# ConnectorIn.net
KiCad netlist of a schematic drawn in Altium Designer
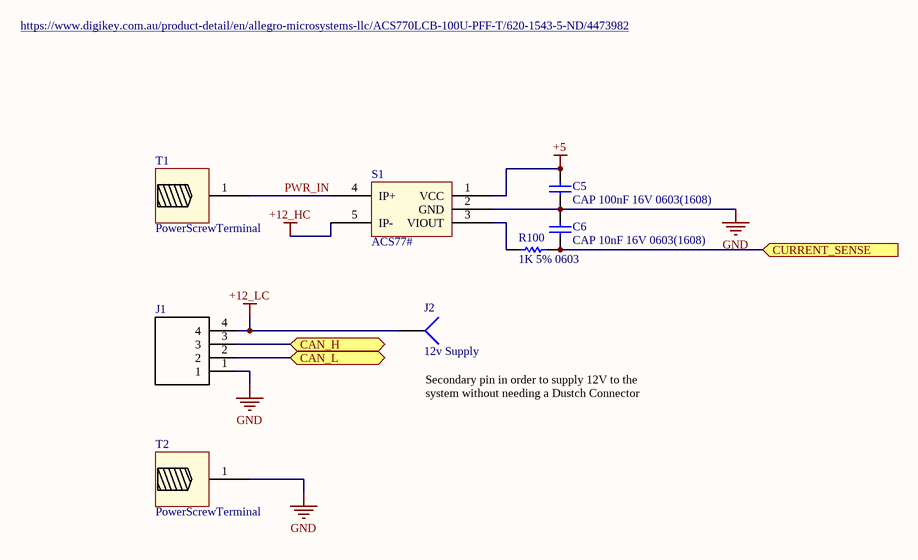
[diagram p0: ConnectorIn.SchDoc]

(export (version "E")
  (design (tool "Eeschema 10.0.6"))
  (components
    (comp (ref "C5")
      (value "CAP 100nF 16V 0603(1608)")
      (footprint "CAPC0603(1608)100_M")
      (description "CAP 100nF 16V ±5% 0603 (1608 Metric) Thickness 1mm SMD")
      (fields (field (name "TOLERANCE") "Â±5%"))
      (libsource (lib "Altium Content Vault") (part "CAP"))
    )
    (comp (ref "C6")
      (value "CAP 10nF 16V 0603(1608)")
      (footprint "CAPC0603(1608)100_M")
      (description "CAP 10nF 16V ±5% 0603 (1608 Metric) Thickness 1mm SMD")
      (fields (field (name "TOLERANCE") "Â±5%"))
      (libsource (lib "Altium Content Vault") (part "CAP"))
    )
    (comp (ref "J1")
      (value "DT15-4P")
      (footprint "TE_DT15-4P")
      (description "DT Series 4 Position 16 AWG Flange Mount Male Pin Through Hole Receptacle Header")
      (fields (field (name "MF") "TE Connectivity") (field (name "DIGI-KEY_PART_NUMBER") "1734-1030-ND"))
      (libsource (lib "DT15-4P") (part "DT15-4P"))
    )
    (comp (ref "J2")
      (value "12v Supply")
      (footprint "PIN1")
      (description "Socket")
      (fields (field (name "PUBLISHER") "Altium Limited"))
      (libsource (lib "Miscellaneous Connectors") (part "Socket"))
    )
    (comp (ref "R100")
      (value "1K 5% 0603")
      (footprint "RESC0603(1608)_L")
      (description "1K 0.1W 5% 0603 (1608 Metric)  SMD")
      (fields (field (name "TOLERANCE") "5 %") (field (name "POWER") "0.1 W"))
      (libsource (lib "Altium Content Vault") (part "RES"))
    )
    (comp (ref "S1")
      (value "ACS77#")
      (footprint "ACS77#")
      (libsource (lib "HC_PCBConnector") (part "ACS77#"))
    )
    (comp (ref "T1")
      (value "PowerScrewTerminal")
      (footprint "WE_REDCUBE_74650195R")
      (libsource (lib "HC_PCBConnector") (part "PowerScrewTerminal"))
    )
    (comp (ref "T2")
      (value "PowerScrewTerminal")
      (footprint "WE_REDCUBE_74650195R")
      (libsource (lib "HC_PCBConnector") (part "PowerScrewTerminal"))
    )
  )
  (nets
    (net (code "1") (name "+5") (class "Default")
      (node (ref "C5") (pin "2") (pinfunction "2_2") (pintype "passive"))
      (node (ref "S1") (pin "1") (pinfunction "VCC_1") (pintype "passive"))
    )
    (net (code "2") (name "+12_HC") (class "Default")
      (node (ref "S1") (pin "5") (pinfunction "IP-_5") (pintype "passive"))
    )
    (net (code "3") (name "+12_LC") (class "Default")
      (node (ref "J1") (pin "4") (pinfunction "4_4") (pintype "passive"))
      (node (ref "J2") (pin "1") (pinfunction "1_1") (pintype "passive"))
    )
    (net (code "4") (name "/CAN_H") (class "Default")
      (node (ref "J1") (pin "3") (pinfunction "3_3") (pintype "passive"))
    )
    (net (code "5") (name "/CAN_L") (class "Default")
      (node (ref "J1") (pin "2") (pinfunction "2_2") (pintype "passive"))
    )
    (net (code "6") (name "/CURRENT_SENSE") (class "Default")
      (node (ref "C6") (pin "1") (pinfunction "1_1") (pintype "passive"))
      (node (ref "R100") (pin "1") (pinfunction "1_1") (pintype "passive"))
    )
    (net (code "7") (name "/PWR_IN") (class "Default")
      (node (ref "S1") (pin "4") (pinfunction "IP+_4") (pintype "passive"))
      (node (ref "T1") (pin "1") (pinfunction "1_1") (pintype "passive"))
    )
    (net (code "8") (name "GND") (class "Default")
      (node (ref "C5") (pin "1") (pinfunction "1_1") (pintype "passive"))
      (node (ref "C6") (pin "2") (pinfunction "2_2") (pintype "passive"))
      (node (ref "J1") (pin "1") (pinfunction "1_1") (pintype "passive"))
      (node (ref "S1") (pin "2") (pinfunction "GND_2") (pintype "passive"))
      (node (ref "T2") (pin "1") (pinfunction "1_1") (pintype "passive"))
    )
    (net (code "9") (name "Net-(S1-VIOUT)") (class "Default")
      (node (ref "R100") (pin "2") (pinfunction "2_2") (pintype "passive"))
      (node (ref "S1") (pin "3") (pinfunction "VIOUT_3") (pintype "passive"))
    )
  )
)
